# outdoor.net
KiCad netlist of a schematic drawn in EAGLE
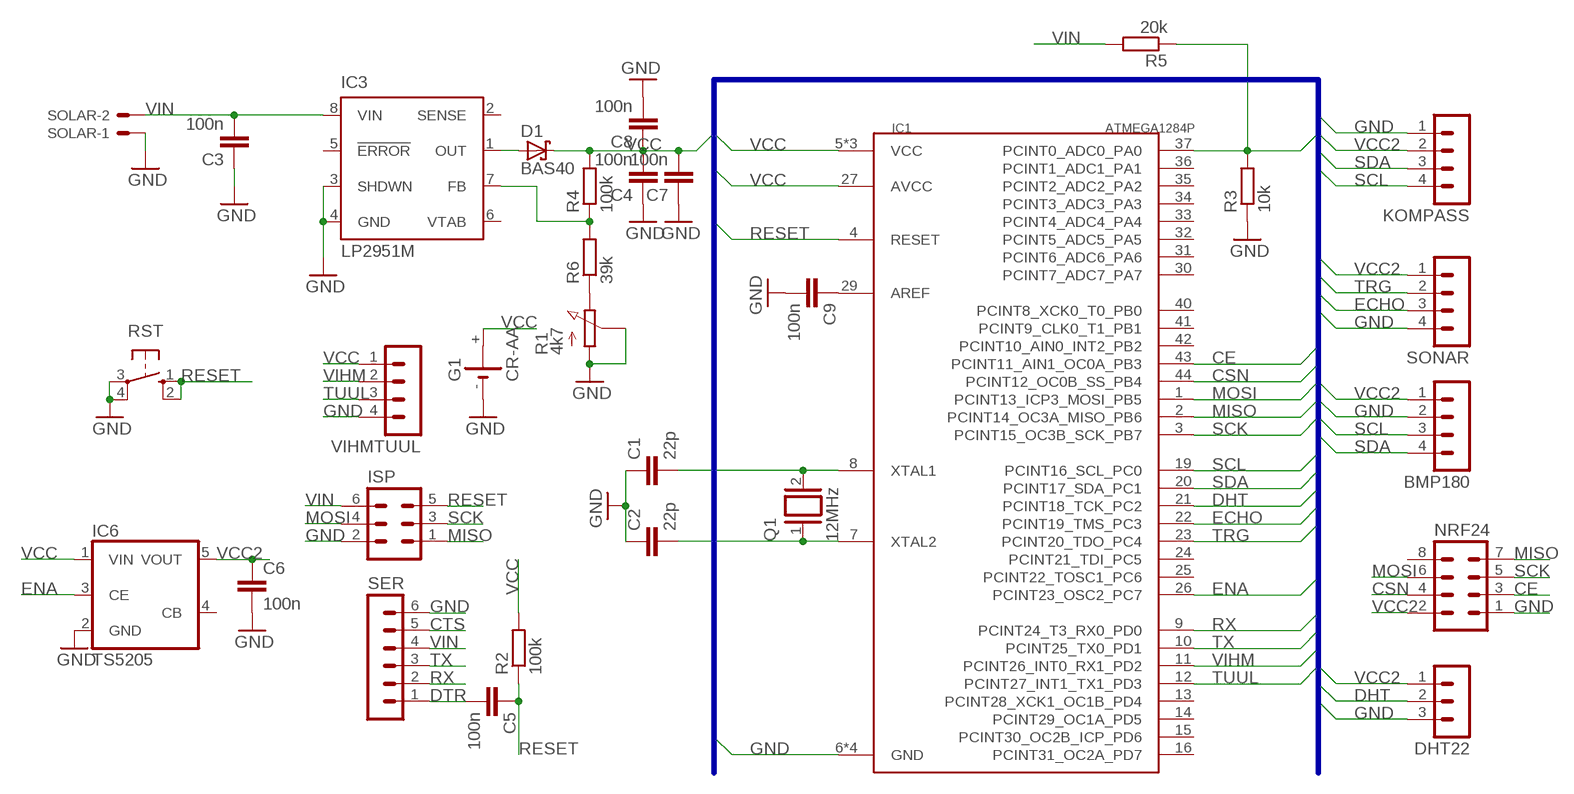
[diagram p0: schematic, sheet 1]

(export (version "E")
  (design (tool "Eeschema 10.0.6"))
  (components
    (comp (ref "BMP180")
      (value "MA04-1")
      (footprint "eagle-import:MA04-1")
      (libsource (lib "eagle-import") (part "MA04-1"))
    )
    (comp (ref "C1")
      (value "22p")
      (footprint "eagle-import:C1206K")
      (libsource (lib "eagle-import") (part "C-EUC1206K"))
    )
    (comp (ref "C2")
      (value "22p")
      (footprint "eagle-import:C1206K")
      (libsource (lib "eagle-import") (part "C-EUC1206K"))
    )
    (comp (ref "C3")
      (value "100n")
      (footprint "eagle-import:C1206K")
      (libsource (lib "eagle-import") (part "C-EUC1206K"))
    )
    (comp (ref "C4")
      (value "100n")
      (footprint "eagle-import:C1206K")
      (libsource (lib "eagle-import") (part "C-EUC1206K"))
    )
    (comp (ref "C5")
      (value "100n")
      (footprint "eagle-import:C1206K")
      (libsource (lib "eagle-import") (part "C-EUC1206K"))
    )
    (comp (ref "C6")
      (value "100n")
      (footprint "eagle-import:C1206K")
      (libsource (lib "eagle-import") (part "C-EUC1206K"))
    )
    (comp (ref "C7")
      (value "100n")
      (footprint "eagle-import:C1206K")
      (libsource (lib "eagle-import") (part "C-EUC1206K"))
    )
    (comp (ref "C8")
      (value "100n")
      (footprint "eagle-import:C1206K")
      (libsource (lib "eagle-import") (part "C-EUC1206K"))
    )
    (comp (ref "C9")
      (value "100n")
      (footprint "eagle-import:C1206K")
      (libsource (lib "eagle-import") (part "C-EUC1206K"))
    )
    (comp (ref "D1")
      (value "BAS40")
      (footprint "eagle-import:SOT23")
      (libsource (lib "eagle-import") (part "BAS40"))
    )
    (comp (ref "DHT22")
      (value "MA03-1")
      (footprint "eagle-import:MA03-1")
      (libsource (lib "eagle-import") (part "MA03-1"))
    )
    (comp (ref "G1")
      (value "CR-AA")
      (footprint "eagle-import:CRAA")
      (libsource (lib "eagle-import") (part "CR-AA"))
    )
    (comp (ref "IC1")
      (value "ATMEGA1284P")
      (footprint "eagle-import:TQFP44")
      (libsource (lib "eagle-import") (part "ATMEGA1284P"))
    )
    (comp (ref "IC3")
      (value "LP2951M")
      (footprint "eagle-import:SO08")
      (fields (field (name "MF") "FAIRCHILD SEMICONDUCTOR") (field (name "MPN") "LP2951CM"))
      (libsource (lib "eagle-import") (part "LP2951M"))
    )
    (comp (ref "IC6")
      (value "TS5205")
      (footprint "eagle-import:SOT25")
      (libsource (lib "eagle-import") (part "TS5205"))
    )
    (comp (ref "ISP")
      (value "MA03-2")
      (footprint "eagle-import:MA03-2")
      (libsource (lib "eagle-import") (part "MA03-2"))
    )
    (comp (ref "KOMPASS")
      (value "MA04-1")
      (footprint "eagle-import:MA04-1")
      (libsource (lib "eagle-import") (part "MA04-1"))
    )
    (comp (ref "NRF24")
      (value "MA04-2")
      (footprint "eagle-import:MA04-2")
      (libsource (lib "eagle-import") (part "MA04-2"))
    )
    (comp (ref "Q1")
      (value "12MHz")
      (footprint "eagle-import:QS")
      (libsource (lib "eagle-import") (part "XTAL/S"))
    )
    (comp (ref "R1")
      (value "4k7")
      (footprint "eagle-import:PC25")
      (fields (field (name "MF") "CLAROSTAT") (field (name "MPN") "308NPC25KS"))
      (libsource (lib "eagle-import") (part "PC25"))
    )
    (comp (ref "R2")
      (value "100k")
      (footprint "eagle-import:M1206")
      (libsource (lib "eagle-import") (part "R-EU_M1206"))
    )
    (comp (ref "R3")
      (value "10k")
      (footprint "eagle-import:M1206")
      (libsource (lib "eagle-import") (part "R-EU_M1206"))
    )
    (comp (ref "R4")
      (value "100k")
      (footprint "eagle-import:M1206")
      (libsource (lib "eagle-import") (part "R-EU_M1206"))
    )
    (comp (ref "R5")
      (value "20k")
      (footprint "eagle-import:M1206")
      (libsource (lib "eagle-import") (part "R-EU_M1206"))
    )
    (comp (ref "R6")
      (value "39k")
      (footprint "eagle-import:M1206")
      (libsource (lib "eagle-import") (part "R-EU_M1206"))
    )
    (comp (ref "RST")
      (value "10-XX")
      (footprint "eagle-import:B3F-10XX")
      (fields (field (name "MPN") "B3F-1000"))
      (libsource (lib "eagle-import") (part "10-XX"))
    )
    (comp (ref "SER")
      (value "MA06-1")
      (footprint "eagle-import:MA06-1")
      (libsource (lib "eagle-import") (part "MA06-1"))
    )
    (comp (ref "SOLAR")
      (value "22-23-2021")
      (footprint "eagle-import:22-23-2021")
      (fields (field (name "MF") "MOLEX"))
      (libsource (lib "eagle-import") (part "22-23-2021"))
    )
    (comp (ref "SONAR")
      (value "MA04-1")
      (footprint "eagle-import:MA04-1")
      (libsource (lib "eagle-import") (part "MA04-1"))
    )
    (comp (ref "VIHMTUUL")
      (value "MA04-1")
      (footprint "eagle-import:MA04-1")
      (libsource (lib "eagle-import") (part "MA04-1"))
    )
  )
  (nets
    (net (code "1") (name "/CE") (class "Default")
      (node (ref "IC1") (pin "43") (pinfunction "PCINT11_AIN1_OC0A_PB3_43") (pintype "bidirectional"))
      (node (ref "NRF24") (pin "3") (pinfunction "3_3") (pintype "passive"))
    )
    (net (code "2") (name "/CSN") (class "Default")
      (node (ref "IC1") (pin "44") (pinfunction "PCINT12_OC0B_SS_PB4_44") (pintype "bidirectional"))
      (node (ref "NRF24") (pin "4") (pinfunction "4_4") (pintype "passive"))
    )
    (net (code "3") (name "/CTS") (class "Default")
      (node (ref "SER") (pin "5") (pinfunction "5_5") (pintype "passive"))
    )
    (net (code "4") (name "/DHT") (class "Default")
      (node (ref "DHT22") (pin "2") (pinfunction "2_2") (pintype "passive"))
      (node (ref "IC1") (pin "21") (pinfunction "PCINT18_TCK_PC2_21") (pintype "bidirectional"))
    )
    (net (code "5") (name "/DTR") (class "Default")
      (node (ref "C5") (pin "2") (pinfunction "2_2") (pintype "passive"))
      (node (ref "SER") (pin "1") (pinfunction "1_1") (pintype "passive"))
    )
    (net (code "6") (name "/ECHO") (class "Default")
      (node (ref "IC1") (pin "22") (pinfunction "PCINT19_TMS_PC3_22") (pintype "bidirectional"))
      (node (ref "SONAR") (pin "3") (pinfunction "3_3") (pintype "passive"))
    )
    (net (code "7") (name "/ENA") (class "Default")
      (node (ref "IC1") (pin "26") (pinfunction "PCINT23_OSC2_PC7_26") (pintype "bidirectional"))
      (node (ref "IC6") (pin "3") (pinfunction "CE_3") (pintype "input"))
    )
    (net (code "8") (name "/MISO") (class "Default")
      (node (ref "IC1") (pin "2") (pinfunction "PCINT14_OC3A_MISO_PB6_2") (pintype "bidirectional"))
      (node (ref "ISP") (pin "1") (pinfunction "1_1") (pintype "passive"))
      (node (ref "NRF24") (pin "7") (pinfunction "7_7") (pintype "passive"))
    )
    (net (code "9") (name "/MOSI") (class "Default")
      (node (ref "IC1") (pin "1") (pinfunction "PCINT13_ICP3_MOSI_PB5_1") (pintype "bidirectional"))
      (node (ref "ISP") (pin "4") (pinfunction "4_4") (pintype "passive"))
      (node (ref "NRF24") (pin "6") (pinfunction "6_6") (pintype "passive"))
    )
    (net (code "10") (name "/RESET") (class "Default")
      (node (ref "C5") (pin "1") (pinfunction "1_1") (pintype "passive"))
      (node (ref "IC1") (pin "4") (pinfunction "RESET_4") (pintype "bidirectional"))
      (node (ref "ISP") (pin "5") (pinfunction "5_5") (pintype "passive"))
      (node (ref "R2") (pin "1") (pinfunction "1_1") (pintype "passive"))
      (node (ref "RST") (pin "1") (pinfunction "S_1") (pintype "passive"))
      (node (ref "RST") (pin "2") (pinfunction "S1_2") (pintype "passive"))
    )
    (net (code "11") (name "/RX") (class "Default")
      (node (ref "IC1") (pin "9") (pinfunction "PCINT24_T3_RX0_PD0_9") (pintype "bidirectional"))
      (node (ref "SER") (pin "2") (pinfunction "2_2") (pintype "passive"))
    )
    (net (code "12") (name "/SCK") (class "Default")
      (node (ref "IC1") (pin "3") (pinfunction "PCINT15_OC3B_SCK_PB7_3") (pintype "bidirectional"))
      (node (ref "ISP") (pin "3") (pinfunction "3_3") (pintype "passive"))
      (node (ref "NRF24") (pin "5") (pinfunction "5_5") (pintype "passive"))
    )
    (net (code "13") (name "/SCL") (class "Default")
      (node (ref "BMP180") (pin "3") (pinfunction "3_3") (pintype "passive"))
      (node (ref "IC1") (pin "19") (pinfunction "PCINT16_SCL_PC0_19") (pintype "bidirectional"))
      (node (ref "KOMPASS") (pin "4") (pinfunction "4_4") (pintype "passive"))
    )
    (net (code "14") (name "/SDA") (class "Default")
      (node (ref "BMP180") (pin "4") (pinfunction "4_4") (pintype "passive"))
      (node (ref "IC1") (pin "20") (pinfunction "PCINT17_SDA_PC1_20") (pintype "bidirectional"))
      (node (ref "KOMPASS") (pin "3") (pinfunction "3_3") (pintype "passive"))
    )
    (net (code "15") (name "/TRG") (class "Default")
      (node (ref "IC1") (pin "23") (pinfunction "PCINT20_TDO_PC4_23") (pintype "bidirectional"))
      (node (ref "SONAR") (pin "2") (pinfunction "2_2") (pintype "passive"))
    )
    (net (code "16") (name "/TUUL") (class "Default")
      (node (ref "IC1") (pin "12") (pinfunction "PCINT27_INT1_TX1_PD3_12") (pintype "bidirectional"))
      (node (ref "VIHMTUUL") (pin "3") (pinfunction "3_3") (pintype "passive"))
    )
    (net (code "17") (name "/TX") (class "Default")
      (node (ref "IC1") (pin "10") (pinfunction "PCINT25_TX0_PD1_10") (pintype "bidirectional"))
      (node (ref "SER") (pin "3") (pinfunction "3_3") (pintype "passive"))
    )
    (net (code "18") (name "/VCC") (class "Default")
      (node (ref "C4") (pin "2") (pinfunction "2_2") (pintype "passive"))
      (node (ref "C7") (pin "2") (pinfunction "2_2") (pintype "passive"))
      (node (ref "C8") (pin "1") (pinfunction "1_1") (pintype "passive"))
      (node (ref "D1") (pin "3") (pinfunction "C_3") (pintype "passive"))
      (node (ref "G1") (pin "+") (pinfunction "+_+") (pintype "passive"))
      (node (ref "IC1") (pin "17") (pinfunction "VCC_17") (pintype "bidirectional"))
      (node (ref "IC1") (pin "27") (pinfunction "AVCC_27") (pintype "bidirectional"))
      (node (ref "IC1") (pin "38") (pinfunction "VCC_38") (pintype "bidirectional"))
      (node (ref "IC1") (pin "5") (pinfunction "VCC_5") (pintype "bidirectional"))
      (node (ref "IC6") (pin "1") (pinfunction "VIN_1") (pintype "input"))
      (node (ref "R2") (pin "2") (pinfunction "2_2") (pintype "passive"))
      (node (ref "R4") (pin "2") (pinfunction "2_2") (pintype "passive"))
      (node (ref "VIHMTUUL") (pin "1") (pinfunction "1_1") (pintype "passive"))
    )
    (net (code "19") (name "/VCC2") (class "Default")
      (node (ref "BMP180") (pin "1") (pinfunction "1_1") (pintype "passive"))
      (node (ref "C6") (pin "1") (pinfunction "1_1") (pintype "passive"))
      (node (ref "DHT22") (pin "1") (pinfunction "1_1") (pintype "passive"))
      (node (ref "IC6") (pin "5") (pinfunction "VOUT_5") (pintype "passive"))
      (node (ref "KOMPASS") (pin "2") (pinfunction "2_2") (pintype "passive"))
      (node (ref "NRF24") (pin "2") (pinfunction "2_2") (pintype "passive"))
      (node (ref "SONAR") (pin "1") (pinfunction "1_1") (pintype "passive"))
    )
    (net (code "20") (name "/VIHM") (class "Default")
      (node (ref "IC1") (pin "11") (pinfunction "PCINT26_INT0_RX1_PD2_11") (pintype "bidirectional"))
      (node (ref "VIHMTUUL") (pin "2") (pinfunction "2_2") (pintype "passive"))
    )
    (net (code "21") (name "/VIN") (class "Default")
      (node (ref "C3") (pin "2") (pinfunction "2_2") (pintype "passive"))
      (node (ref "IC3") (pin "8") (pinfunction "VIN_8") (pintype "input"))
      (node (ref "ISP") (pin "6") (pinfunction "6_6") (pintype "passive"))
      (node (ref "R5") (pin "2") (pinfunction "2_2") (pintype "passive"))
      (node (ref "SER") (pin "4") (pinfunction "4_4") (pintype "passive"))
      (node (ref "SOLAR") (pin "2") (pinfunction "S_2") (pintype "passive"))
    )
    (net (code "22") (name "GND") (class "Default")
      (node (ref "BMP180") (pin "2") (pinfunction "2_2") (pintype "passive"))
      (node (ref "C1") (pin "1") (pinfunction "1_1") (pintype "passive"))
      (node (ref "C2") (pin "1") (pinfunction "1_1") (pintype "passive"))
      (node (ref "C3") (pin "1") (pinfunction "1_1") (pintype "passive"))
      (node (ref "C4") (pin "1") (pinfunction "1_1") (pintype "passive"))
      (node (ref "C6") (pin "2") (pinfunction "2_2") (pintype "passive"))
      (node (ref "C7") (pin "1") (pinfunction "1_1") (pintype "passive"))
      (node (ref "C8") (pin "2") (pinfunction "2_2") (pintype "passive"))
      (node (ref "C9") (pin "2") (pinfunction "2_2") (pintype "passive"))
      (node (ref "DHT22") (pin "3") (pinfunction "3_3") (pintype "passive"))
      (node (ref "G1") (pin "-") (pinfunction "-_-") (pintype "passive"))
      (node (ref "IC1") (pin "18") (pinfunction "GND_18") (pintype "bidirectional"))
      (node (ref "IC1") (pin "28") (pinfunction "GND_28") (pintype "bidirectional"))
      (node (ref "IC1") (pin "39") (pinfunction "GND_39") (pintype "bidirectional"))
      (node (ref "IC1") (pin "6") (pinfunction "GND_6") (pintype "bidirectional"))
      (node (ref "IC3") (pin "3") (pinfunction "SHDWN_3") (pintype "input"))
      (node (ref "IC3") (pin "4") (pinfunction "GND_4") (pintype "power_in"))
      (node (ref "IC6") (pin "2") (pinfunction "GND_2") (pintype "passive"))
      (node (ref "ISP") (pin "2") (pinfunction "2_2") (pintype "passive"))
      (node (ref "KOMPASS") (pin "1") (pinfunction "1_1") (pintype "passive"))
      (node (ref "NRF24") (pin "1") (pinfunction "1_1") (pintype "passive"))
      (node (ref "R1") (pin "A") (pinfunction "A_A") (pintype "passive"))
      (node (ref "R1") (pin "S") (pinfunction "S_S") (pintype "passive"))
      (node (ref "R3") (pin "1") (pinfunction "1_1") (pintype "passive"))
      (node (ref "RST") (pin "3") (pinfunction "P_3") (pintype "passive"))
      (node (ref "RST") (pin "4") (pinfunction "P1_4") (pintype "passive"))
      (node (ref "SER") (pin "6") (pinfunction "6_6") (pintype "passive"))
      (node (ref "SOLAR") (pin "1") (pinfunction "S_1") (pintype "passive"))
      (node (ref "SONAR") (pin "4") (pinfunction "4_4") (pintype "passive"))
      (node (ref "VIHMTUUL") (pin "4") (pinfunction "4_4") (pintype "passive"))
    )
    (net (code "23") (name "Net-(D1-A)") (class "Default")
      (node (ref "D1") (pin "1") (pinfunction "A_1") (pintype "passive"))
      (node (ref "IC3") (pin "1") (pinfunction "OUT_1") (pintype "output"))
    )
    (net (code "24") (name "Net-(IC1-AREF)") (class "Default")
      (node (ref "C9") (pin "1") (pinfunction "1_1") (pintype "passive"))
      (node (ref "IC1") (pin "29") (pinfunction "AREF_29") (pintype "bidirectional"))
    )
    (net (code "25") (name "Net-(IC1-PCINT0_ADC0_PA0)") (class "Default")
      (node (ref "IC1") (pin "37") (pinfunction "PCINT0_ADC0_PA0_37") (pintype "bidirectional"))
      (node (ref "R3") (pin "2") (pinfunction "2_2") (pintype "passive"))
      (node (ref "R5") (pin "1") (pinfunction "1_1") (pintype "passive"))
    )
    (net (code "26") (name "Net-(IC1-XTAL1)") (class "Default")
      (node (ref "C1") (pin "2") (pinfunction "2_2") (pintype "passive"))
      (node (ref "IC1") (pin "8") (pinfunction "XTAL1_8") (pintype "bidirectional"))
      (node (ref "Q1") (pin "2") (pinfunction "2_2") (pintype "passive"))
    )
    (net (code "27") (name "Net-(IC1-XTAL2)") (class "Default")
      (node (ref "C2") (pin "2") (pinfunction "2_2") (pintype "passive"))
      (node (ref "IC1") (pin "7") (pinfunction "XTAL2_7") (pintype "bidirectional"))
      (node (ref "Q1") (pin "1") (pinfunction "1_1") (pintype "passive"))
    )
    (net (code "28") (name "Net-(IC3-FB)") (class "Default")
      (node (ref "IC3") (pin "7") (pinfunction "FB_7") (pintype "input"))
      (node (ref "R4") (pin "1") (pinfunction "1_1") (pintype "passive"))
      (node (ref "R6") (pin "2") (pinfunction "2_2") (pintype "passive"))
    )
    (net (code "29") (name "Net-(R1-PadE)") (class "Default")
      (node (ref "R1") (pin "E") (pinfunction "E_E") (pintype "passive"))
      (node (ref "R6") (pin "1") (pinfunction "1_1") (pintype "passive"))
    )
    (net (code "30") (name "unconnected-(G1-+-Pad+@1)") (class "Default")
      (node (ref "G1") (pin "+@1") (pinfunction "+_+@1") (pintype "passive"))
    )
    (net (code "31") (name "unconnected-(IC1-PCINT1_ADC1_PA1-Pad36)") (class "Default")
      (node (ref "IC1") (pin "36") (pinfunction "PCINT1_ADC1_PA1_36") (pintype "bidirectional"))
    )
    (net (code "32") (name "unconnected-(IC1-PCINT2_ADC2_PA2-Pad35)") (class "Default")
      (node (ref "IC1") (pin "35") (pinfunction "PCINT2_ADC2_PA2_35") (pintype "bidirectional"))
    )
    (net (code "33") (name "unconnected-(IC1-PCINT3_ADC3_PA3-Pad34)") (class "Default")
      (node (ref "IC1") (pin "34") (pinfunction "PCINT3_ADC3_PA3_34") (pintype "bidirectional"))
    )
    (net (code "34") (name "unconnected-(IC1-PCINT4_ADC4_PA4-Pad33)") (class "Default")
      (node (ref "IC1") (pin "33") (pinfunction "PCINT4_ADC4_PA4_33") (pintype "bidirectional"))
    )
    (net (code "35") (name "unconnected-(IC1-PCINT5_ADC5_PA5-Pad32)") (class "Default")
      (node (ref "IC1") (pin "32") (pinfunction "PCINT5_ADC5_PA5_32") (pintype "bidirectional"))
    )
    (net (code "36") (name "unconnected-(IC1-PCINT6_ADC6_PA6-Pad31)") (class "Default")
      (node (ref "IC1") (pin "31") (pinfunction "PCINT6_ADC6_PA6_31") (pintype "bidirectional"))
    )
    (net (code "37") (name "unconnected-(IC1-PCINT7_ADC7_PA7-Pad30)") (class "Default")
      (node (ref "IC1") (pin "30") (pinfunction "PCINT7_ADC7_PA7_30") (pintype "bidirectional"))
    )
    (net (code "38") (name "unconnected-(IC1-PCINT8_XCK0_T0_PB0-Pad40)") (class "Default")
      (node (ref "IC1") (pin "40") (pinfunction "PCINT8_XCK0_T0_PB0_40") (pintype "bidirectional"))
    )
    (net (code "39") (name "unconnected-(IC1-PCINT9_CLK0_T1_PB1-Pad41)") (class "Default")
      (node (ref "IC1") (pin "41") (pinfunction "PCINT9_CLK0_T1_PB1_41") (pintype "bidirectional"))
    )
    (net (code "40") (name "unconnected-(IC1-PCINT10_AIN0_INT2_PB2-Pad42)") (class "Default")
      (node (ref "IC1") (pin "42") (pinfunction "PCINT10_AIN0_INT2_PB2_42") (pintype "bidirectional"))
    )
    (net (code "41") (name "unconnected-(IC1-PCINT21_TDI_PC5-Pad24)") (class "Default")
      (node (ref "IC1") (pin "24") (pinfunction "PCINT21_TDI_PC5_24") (pintype "bidirectional"))
    )
    (net (code "42") (name "unconnected-(IC1-PCINT22_TOSC1_PC6-Pad25)") (class "Default")
      (node (ref "IC1") (pin "25") (pinfunction "PCINT22_TOSC1_PC6_25") (pintype "bidirectional"))
    )
    (net (code "43") (name "unconnected-(IC1-PCINT28_XCK1_OC1B_PD4-Pad13)") (class "Default")
      (node (ref "IC1") (pin "13") (pinfunction "PCINT28_XCK1_OC1B_PD4_13") (pintype "bidirectional"))
    )
    (net (code "44") (name "unconnected-(IC1-PCINT29_OC1A_PD5-Pad14)") (class "Default")
      (node (ref "IC1") (pin "14") (pinfunction "PCINT29_OC1A_PD5_14") (pintype "bidirectional"))
    )
    (net (code "45") (name "unconnected-(IC1-PCINT30_OC2B_ICP_PD6-Pad15)") (class "Default")
      (node (ref "IC1") (pin "15") (pinfunction "PCINT30_OC2B_ICP_PD6_15") (pintype "bidirectional"))
    )
    (net (code "46") (name "unconnected-(IC1-PCINT31_OC2A_PD7-Pad16)") (class "Default")
      (node (ref "IC1") (pin "16") (pinfunction "PCINT31_OC2A_PD7_16") (pintype "bidirectional"))
    )
    (net (code "47") (name "unconnected-(IC3-SENSE-Pad2)") (class "Default")
      (node (ref "IC3") (pin "2") (pinfunction "SENSE_2") (pintype "input"))
    )
    (net (code "48") (name "unconnected-(IC3-VTAB-Pad6)") (class "Default")
      (node (ref "IC3") (pin "6") (pinfunction "VTAB_6") (pintype "input"))
    )
    (net (code "49") (name "unconnected-(IC3-~{ERROR}-Pad5)") (class "Default")
      (node (ref "IC3") (pin "5") (pinfunction "~{ERROR}_5") (pintype "output"))
    )
    (net (code "50") (name "unconnected-(IC6-CB-Pad4)") (class "Default")
      (node (ref "IC6") (pin "4") (pinfunction "CB_4") (pintype "input"))
    )
    (net (code "51") (name "unconnected-(NRF24-Pad8)") (class "Default")
      (node (ref "NRF24") (pin "8") (pinfunction "8_8") (pintype "passive"))
    )
  )
)
